# untitled.net
KiCad netlist of a schematic drawn in EAGLE
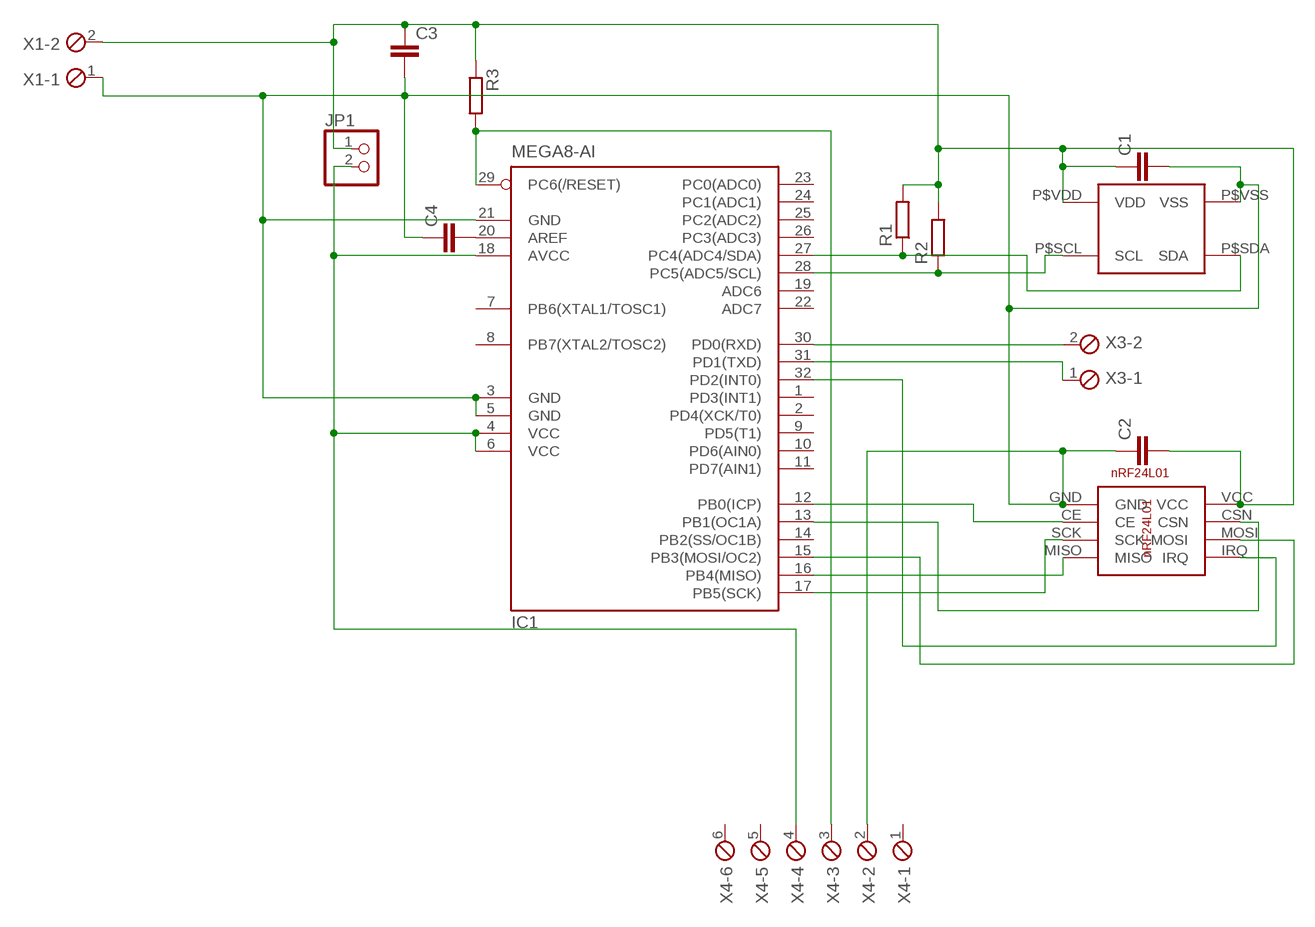
[diagram p0: schematic, sheet 1]

(export (version "E")
  (design (tool "Eeschema 10.0.6"))
  (components
    (comp (ref "C1")
      (value "C-EUC1206")
      (footprint "eagle-import:C1206")
      (libsource (lib "eagle-import") (part "resistor_C-EUC1206"))
    )
    (comp (ref "C2")
      (value "C-EUC0805")
      (footprint "eagle-import:C0805")
      (libsource (lib "eagle-import") (part "resistor_C-EUC0805"))
    )
    (comp (ref "C3")
      (value "C-EU025-060X050")
      (footprint "eagle-import:C025-060X050")
      (libsource (lib "eagle-import") (part "C-EU025-060X050"))
    )
    (comp (ref "C4")
      (value "C-EUC0805K")
      (footprint "eagle-import:C0805K")
      (libsource (lib "eagle-import") (part "resistor_C-EUC0805K"))
    )
    (comp (ref "IC1")
      (value "MEGA8-AI")
      (footprint "eagle-import:TQFP32-08")
      (fields (field (name "MPN") "ATMEGA8-16AU"))
      (libsource (lib "eagle-import") (part "MEGA8-AI"))
    )
    (comp (ref "JP1")
      (value "PINHD-1X2")
      (footprint "eagle-import:1X02")
      (libsource (lib "eagle-import") (part "PINHD-1X2"))
    )
    (comp (ref "R1")
      (value "R-EU_R0805")
      (footprint "eagle-import:R0805")
      (libsource (lib "eagle-import") (part "R-EU_R0805"))
    )
    (comp (ref "R2")
      (value "R-EU_R0805")
      (footprint "eagle-import:R0805")
      (libsource (lib "eagle-import") (part "R-EU_R0805"))
    )
    (comp (ref "R3")
      (value "R-EU_R0805")
      (footprint "eagle-import:R0805")
      (libsource (lib "eagle-import") (part "R-EU_R0805"))
    )
    (comp (ref "U$1")
      (value "SHT21")
      (footprint "eagle-import:DFN6")
      (libsource (lib "eagle-import") (part "SHT21"))
    )
    (comp (ref "U$2")
      (value "NRF24L01B")
      (footprint "eagle-import:B1")
      (libsource (lib "eagle-import") (part "NRF24L01B"))
    )
    (comp (ref "X1")
      (value "MPT2")
      (footprint "eagle-import:2POL254")
      (libsource (lib "eagle-import") (part "MPT2"))
    )
    (comp (ref "X3")
      (value "MPT2")
      (footprint "eagle-import:2POL254")
      (libsource (lib "eagle-import") (part "MPT2"))
    )
    (comp (ref "X4")
      (value "MPT6")
      (footprint "eagle-import:6POL254")
      (fields (field (name "OC_FARNELL") "unknown") (field (name "OC_NEWARK") "unknown"))
      (libsource (lib "eagle-import") (part "MPT6"))
    )
  )
  (nets
    (net (code "1") (name "Net-(IC1-AREF)") (class "Default")
      (node (ref "C4") (pin "2") (pinfunction "2_2") (pintype "passive"))
      (node (ref "IC1") (pin "20") (pinfunction "AREF_20") (pintype "passive"))
    )
    (net (code "2") (name "Net-(IC1-AVCC)") (class "Default")
      (node (ref "IC1") (pin "18") (pinfunction "AVCC_18") (pintype "power_in"))
      (node (ref "IC1") (pin "4") (pinfunction "VCC_4") (pintype "power_in"))
      (node (ref "IC1") (pin "6") (pinfunction "VCC_6") (pintype "power_in"))
      (node (ref "JP1") (pin "2") (pinfunction "2_2") (pintype "passive"))
      (node (ref "X4") (pin "4") (pinfunction "1_4") (pintype "passive"))
    )
    (net (code "3") (name "Net-(IC1-PB0(ICP))") (class "Default")
      (node (ref "IC1") (pin "12") (pinfunction "PB0(ICP)_12") (pintype "bidirectional"))
      (node (ref "U$2") (pin "CE") (pinfunction "CE_CE") (pintype "bidirectional"))
    )
    (net (code "4") (name "Net-(IC1-PB1(OC1A))") (class "Default")
      (node (ref "IC1") (pin "13") (pinfunction "PB1(OC1A)_13") (pintype "bidirectional"))
      (node (ref "U$2") (pin "CSN") (pinfunction "CSN_CSN") (pintype "bidirectional"))
    )
    (net (code "5") (name "Net-(IC1-PB3(MOSI{slash}OC2))") (class "Default")
      (node (ref "IC1") (pin "15") (pinfunction "PB3(MOSI/OC2)_15") (pintype "bidirectional"))
      (node (ref "U$2") (pin "MOSI") (pinfunction "MOSI_MOSI") (pintype "bidirectional"))
    )
    (net (code "6") (name "Net-(IC1-PB4(MISO))") (class "Default")
      (node (ref "IC1") (pin "16") (pinfunction "PB4(MISO)_16") (pintype "bidirectional"))
      (node (ref "U$2") (pin "MISO") (pinfunction "MISO_MISO") (pintype "bidirectional"))
    )
    (net (code "7") (name "Net-(IC1-PB5(SCK))") (class "Default")
      (node (ref "IC1") (pin "17") (pinfunction "PB5(SCK)_17") (pintype "bidirectional"))
      (node (ref "U$2") (pin "SCK") (pinfunction "SCK_SCK") (pintype "bidirectional"))
    )
    (net (code "8") (name "Net-(IC1-PC4(ADC4{slash}SDA))") (class "Default")
      (node (ref "IC1") (pin "27") (pinfunction "PC4(ADC4/SDA)_27") (pintype "bidirectional"))
      (node (ref "R1") (pin "1") (pinfunction "1_1") (pintype "passive"))
      (node (ref "U$1") (pin "P$SDA") (pinfunction "SDA_P$SDA") (pintype "bidirectional"))
    )
    (net (code "9") (name "Net-(IC1-PC5(ADC5{slash}SCL))") (class "Default")
      (node (ref "IC1") (pin "28") (pinfunction "PC5(ADC5/SCL)_28") (pintype "bidirectional"))
      (node (ref "R2") (pin "1") (pinfunction "1_1") (pintype "passive"))
      (node (ref "U$1") (pin "P$SCL") (pinfunction "SCL_P$SCL") (pintype "bidirectional"))
    )
    (net (code "10") (name "Net-(IC1-PC6({slash}RESET))") (class "Default")
      (node (ref "IC1") (pin "29") (pinfunction "PC6(/RESET)_29") (pintype "bidirectional"))
      (node (ref "R3") (pin "2") (pinfunction "2_2") (pintype "passive"))
      (node (ref "X4") (pin "3") (pinfunction "1_3") (pintype "passive"))
    )
    (net (code "11") (name "Net-(IC1-PD0(RXD))") (class "Default")
      (node (ref "IC1") (pin "30") (pinfunction "PD0(RXD)_30") (pintype "bidirectional"))
      (node (ref "X3") (pin "2") (pinfunction "1_2") (pintype "passive"))
    )
    (net (code "12") (name "Net-(IC1-PD1(TXD))") (class "Default")
      (node (ref "IC1") (pin "31") (pinfunction "PD1(TXD)_31") (pintype "bidirectional"))
      (node (ref "X3") (pin "1") (pinfunction "1_1") (pintype "passive"))
    )
    (net (code "13") (name "Net-(IC1-PD2(INT0))") (class "Default")
      (node (ref "IC1") (pin "32") (pinfunction "PD2(INT0)_32") (pintype "bidirectional"))
      (node (ref "U$2") (pin "IRQ") (pinfunction "IRQ_IRQ") (pintype "bidirectional"))
    )
    (net (code "14") (name "Net-(U$1-VDD)") (class "Default")
      (node (ref "C1") (pin "1") (pinfunction "1_1") (pintype "passive"))
      (node (ref "C2") (pin "2") (pinfunction "2_2") (pintype "passive"))
      (node (ref "C3") (pin "1") (pinfunction "1_1") (pintype "passive"))
      (node (ref "JP1") (pin "1") (pinfunction "1_1") (pintype "passive"))
      (node (ref "R1") (pin "2") (pinfunction "2_2") (pintype "passive"))
      (node (ref "R2") (pin "2") (pinfunction "2_2") (pintype "passive"))
      (node (ref "R3") (pin "1") (pinfunction "1_1") (pintype "passive"))
      (node (ref "U$1") (pin "P$VDD") (pinfunction "VDD_P$VDD") (pintype "bidirectional"))
      (node (ref "U$2") (pin "VCC") (pinfunction "VCC_VCC") (pintype "bidirectional"))
      (node (ref "X1") (pin "2") (pinfunction "1_2") (pintype "passive"))
    )
    (net (code "15") (name "Net-(U$1-VSS)") (class "Default")
      (node (ref "C1") (pin "2") (pinfunction "2_2") (pintype "passive"))
      (node (ref "C2") (pin "1") (pinfunction "1_1") (pintype "passive"))
      (node (ref "C3") (pin "2") (pinfunction "2_2") (pintype "passive"))
      (node (ref "C4") (pin "1") (pinfunction "1_1") (pintype "passive"))
      (node (ref "IC1") (pin "21") (pinfunction "GND_21") (pintype "power_in"))
      (node (ref "IC1") (pin "3") (pinfunction "GND_3") (pintype "power_in"))
      (node (ref "IC1") (pin "5") (pinfunction "GND_5") (pintype "power_in"))
      (node (ref "U$1") (pin "P$VSS") (pinfunction "VSS_P$VSS") (pintype "bidirectional"))
      (node (ref "U$2") (pin "GND") (pinfunction "GND_GND") (pintype "bidirectional"))
      (node (ref "X1") (pin "1") (pinfunction "1_1") (pintype "passive"))
      (node (ref "X4") (pin "2") (pinfunction "1_2") (pintype "passive"))
    )
    (net (code "16") (name "unconnected-(IC1-ADC6-Pad19)") (class "Default")
      (node (ref "IC1") (pin "19") (pinfunction "ADC6_19") (pintype "bidirectional"))
    )
    (net (code "17") (name "unconnected-(IC1-ADC7-Pad22)") (class "Default")
      (node (ref "IC1") (pin "22") (pinfunction "ADC7_22") (pintype "bidirectional"))
    )
    (net (code "18") (name "unconnected-(IC1-PB2(SS{slash}OC1B)-Pad14)") (class "Default")
      (node (ref "IC1") (pin "14") (pinfunction "PB2(SS/OC1B)_14") (pintype "bidirectional"))
    )
    (net (code "19") (name "unconnected-(IC1-PB6(XTAL1{slash}TOSC1)-Pad7)") (class "Default")
      (node (ref "IC1") (pin "7") (pinfunction "PB6(XTAL1/TOSC1)_7") (pintype "bidirectional"))
    )
    (net (code "20") (name "unconnected-(IC1-PB7(XTAL2{slash}TOSC2)-Pad8)") (class "Default")
      (node (ref "IC1") (pin "8") (pinfunction "PB7(XTAL2/TOSC2)_8") (pintype "bidirectional"))
    )
    (net (code "21") (name "unconnected-(IC1-PC0(ADC0)-Pad23)") (class "Default")
      (node (ref "IC1") (pin "23") (pinfunction "PC0(ADC0)_23") (pintype "bidirectional"))
    )
    (net (code "22") (name "unconnected-(IC1-PC1(ADC1)-Pad24)") (class "Default")
      (node (ref "IC1") (pin "24") (pinfunction "PC1(ADC1)_24") (pintype "bidirectional"))
    )
    (net (code "23") (name "unconnected-(IC1-PC2(ADC2)-Pad25)") (class "Default")
      (node (ref "IC1") (pin "25") (pinfunction "PC2(ADC2)_25") (pintype "bidirectional"))
    )
    (net (code "24") (name "unconnected-(IC1-PC3(ADC3)-Pad26)") (class "Default")
      (node (ref "IC1") (pin "26") (pinfunction "PC3(ADC3)_26") (pintype "bidirectional"))
    )
    (net (code "25") (name "unconnected-(IC1-PD3(INT1)-Pad1)") (class "Default")
      (node (ref "IC1") (pin "1") (pinfunction "PD3(INT1)_1") (pintype "bidirectional"))
    )
    (net (code "26") (name "unconnected-(IC1-PD4(XCK{slash}T0)-Pad2)") (class "Default")
      (node (ref "IC1") (pin "2") (pinfunction "PD4(XCK/T0)_2") (pintype "bidirectional"))
    )
    (net (code "27") (name "unconnected-(IC1-PD5(T1)-Pad9)") (class "Default")
      (node (ref "IC1") (pin "9") (pinfunction "PD5(T1)_9") (pintype "bidirectional"))
    )
    (net (code "28") (name "unconnected-(IC1-PD6(AIN0)-Pad10)") (class "Default")
      (node (ref "IC1") (pin "10") (pinfunction "PD6(AIN0)_10") (pintype "bidirectional"))
    )
    (net (code "29") (name "unconnected-(IC1-PD7(AIN1)-Pad11)") (class "Default")
      (node (ref "IC1") (pin "11") (pinfunction "PD7(AIN1)_11") (pintype "bidirectional"))
    )
    (net (code "30") (name "unconnected-(X4-Pad1)") (class "Default")
      (node (ref "X4") (pin "1") (pinfunction "1_1") (pintype "passive"))
    )
    (net (code "31") (name "unconnected-(X4E-1-Pad5)") (class "Default")
      (node (ref "X4") (pin "5") (pinfunction "1_5") (pintype "passive"))
    )
    (net (code "32") (name "unconnected-(X4F-1-Pad6)") (class "Default")
      (node (ref "X4") (pin "6") (pinfunction "1_6") (pintype "passive"))
    )
  )
)
